# Sincronismo.net
KiCad netlist of a schematic drawn in Altium Designer
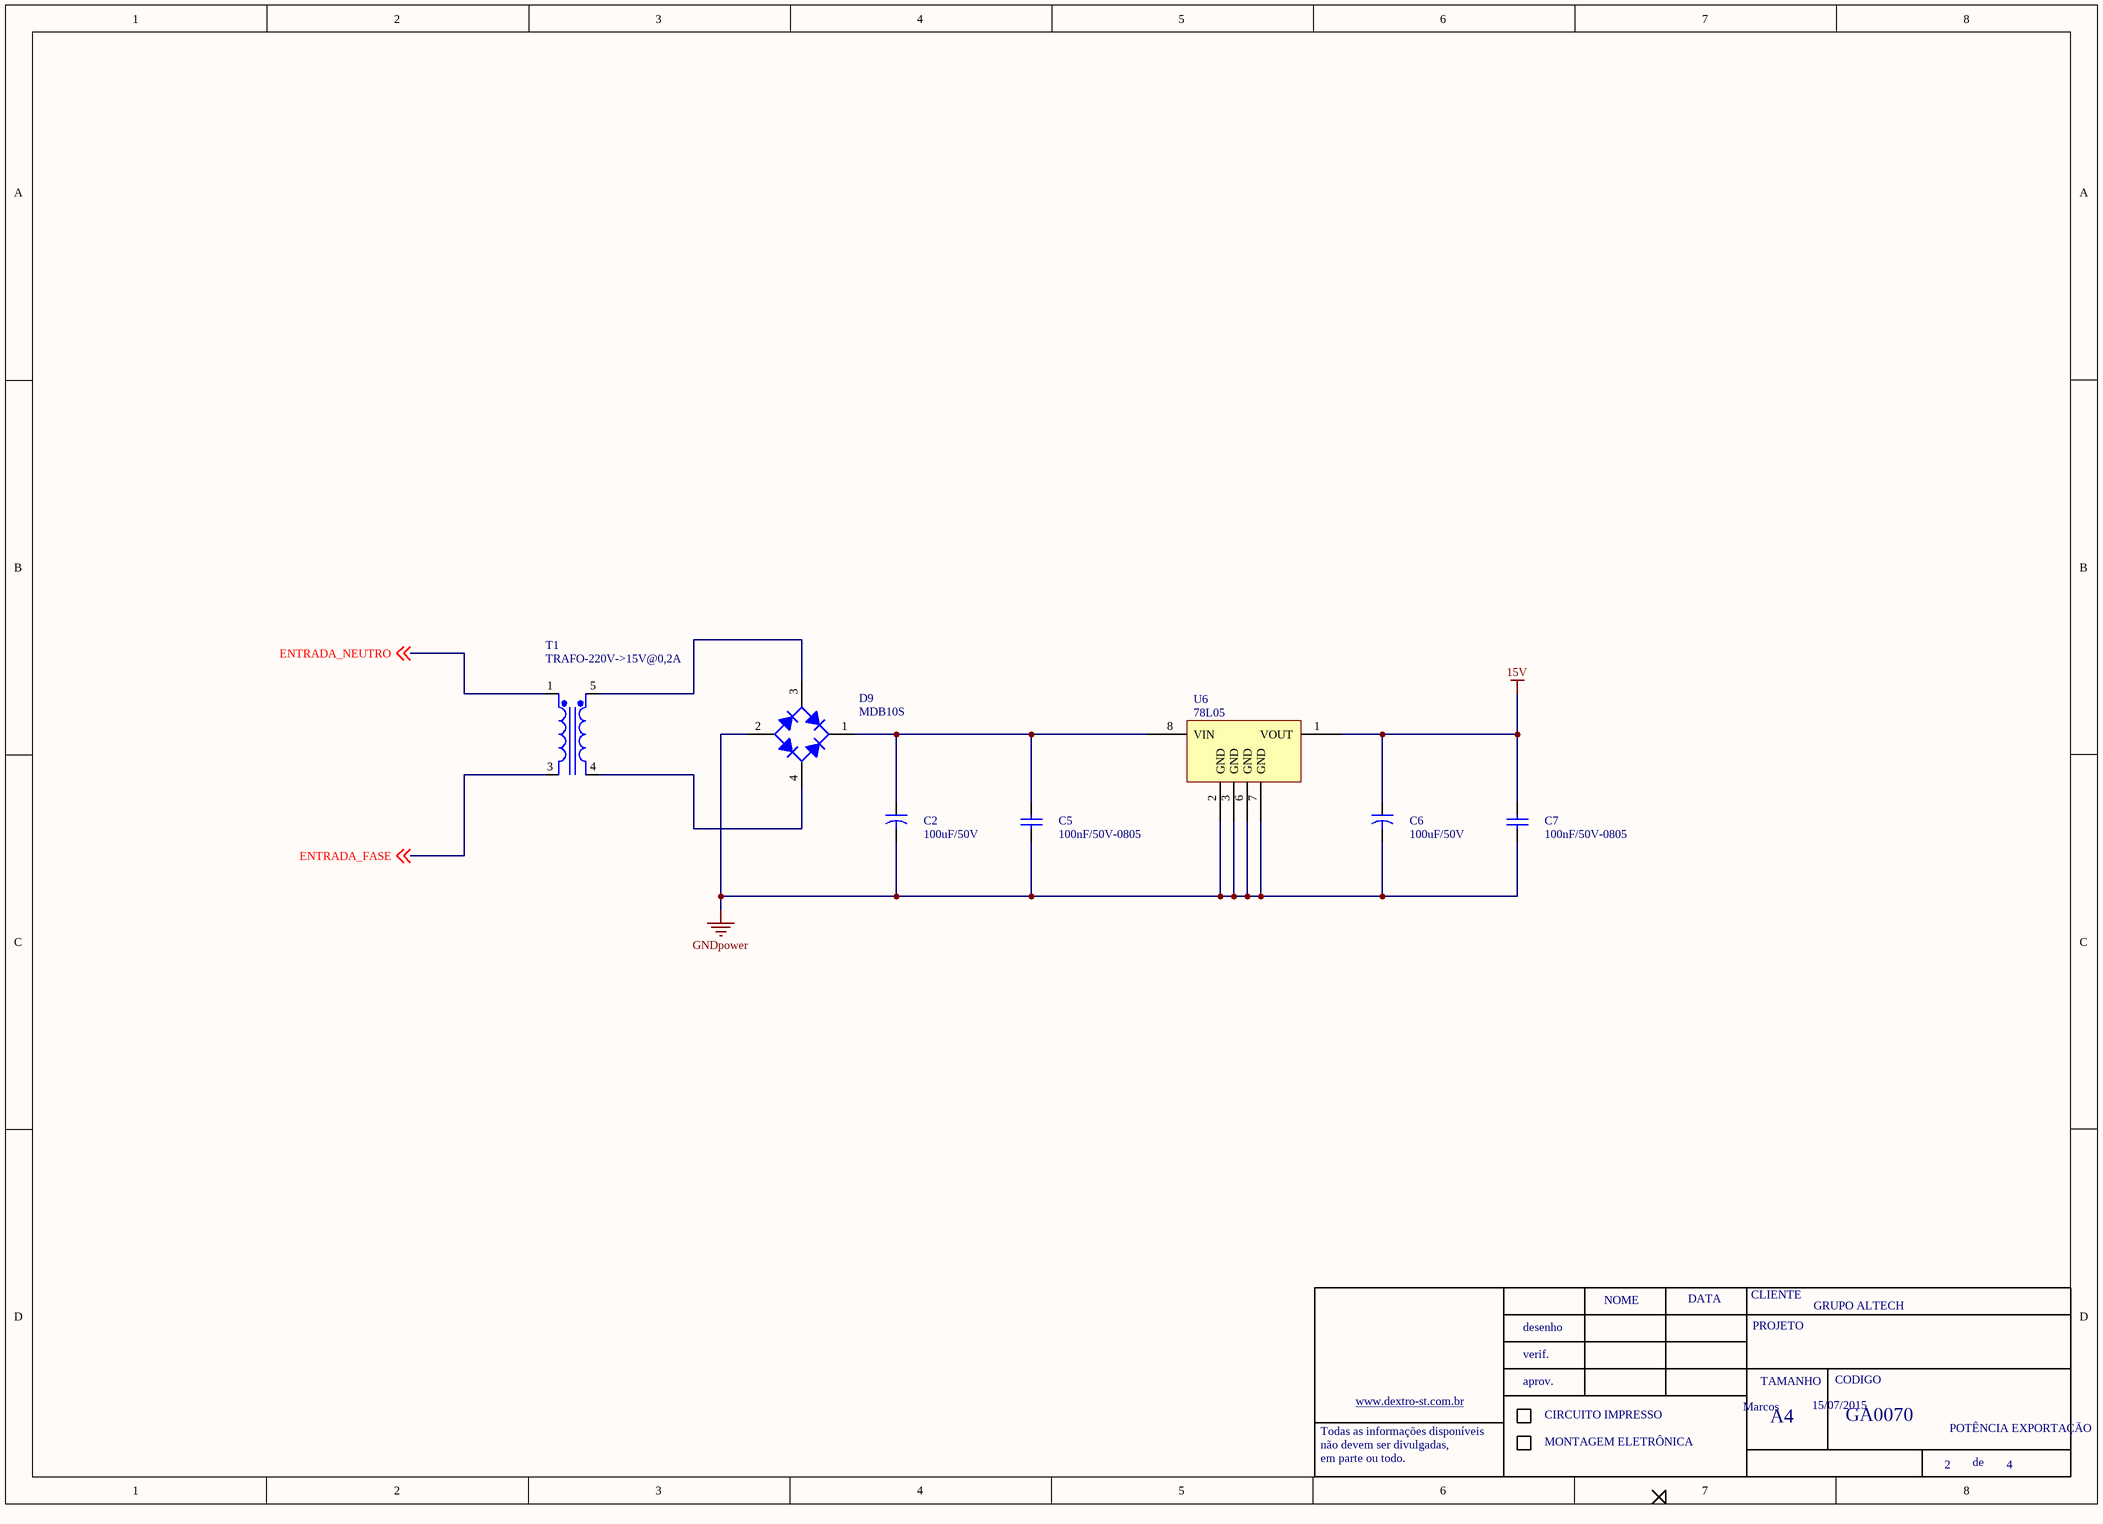
[diagram p0: Sincronismo.SchDoc]

(export (version "E")
  (design (tool "Eeschema 10.0.6"))
  (components
    (comp (ref "C2")
      (value "100uF/50V")
      (footprint "CAP POL 8x12mm")
      (libsource (lib "AquinoLib") (part "100uF/50V"))
    )
    (comp (ref "C5")
      (value "100nF/50V-0805")
      (footprint "0805-REVISADO ONDA")
      (libsource (lib "AquinoLib") (part "100nF/50-0805-NPO"))
    )
    (comp (ref "C6")
      (value "100uF/50V")
      (footprint "CAP POL 8x12mm")
      (libsource (lib "AquinoLib") (part "100uF/50V"))
    )
    (comp (ref "C7")
      (value "100nF/50V-0805")
      (footprint "0805-REVISADO ONDA")
      (libsource (lib "AquinoLib") (part "100nF/50-0805-NPO"))
    )
    (comp (ref "D9")
      (value "MDB10S")
      (footprint "MICRO DIP MDB10S")
      (libsource (lib "AquinoLib") (part "MDB10S"))
    )
    (comp (ref "T1")
      (value "TRAFO-220V->15V@0,2A")
      (description "TRAFO CORRENTE 1A-5V")
      (libsource (lib "ChaveDigital3") (part "TRAFO CORRENTE"))
    )
    (comp (ref "U6")
      (value "78L05")
      (footprint "SOIC-08")
      (libsource (lib "ChaveDigital3") (part "78L05-SOIC"))
    )
  )
  (nets
    (net (code "1") (name "15V") (class "Default")
      (node (ref "C6") (pin "1") (pinfunction "1_1") (pintype "passive"))
      (node (ref "C7") (pin "2") (pinfunction "2_2") (pintype "passive"))
      (node (ref "U6") (pin "1") (pinfunction "VOUT_1") (pintype "passive"))
    )
    (net (code "2") (name "ENTRADA_FASE") (class "Default")
      (node (ref "T1") (pin "3") (pinfunction "3_3") (pintype "passive"))
    )
    (net (code "3") (name "ENTRADA_NEUTRO") (class "Default")
      (node (ref "T1") (pin "1") (pinfunction "1_1") (pintype "passive"))
    )
    (net (code "4") (name "GNDpower") (class "Default")
      (node (ref "C2") (pin "2") (pinfunction "2_2") (pintype "passive"))
      (node (ref "C5") (pin "1") (pinfunction "1_1") (pintype "passive"))
      (node (ref "C6") (pin "2") (pinfunction "2_2") (pintype "passive"))
      (node (ref "C7") (pin "1") (pinfunction "1_1") (pintype "passive"))
      (node (ref "D9") (pin "2") (pinfunction "A_2") (pintype "passive"))
      (node (ref "U6") (pin "2") (pinfunction "GND_2") (pintype "passive"))
      (node (ref "U6") (pin "3") (pinfunction "GND_3") (pintype "passive"))
      (node (ref "U6") (pin "6") (pinfunction "GND_6") (pintype "passive"))
      (node (ref "U6") (pin "7") (pinfunction "GND_7") (pintype "passive"))
    )
    (net (code "5") (name "Net-(D9-C-Pad3)") (class "Default")
      (node (ref "D9") (pin "3") (pinfunction "C_3") (pintype "passive"))
      (node (ref "T1") (pin "5") (pinfunction "5_5") (pintype "passive"))
    )
    (net (code "6") (name "Net-(D9-C-Pad4)") (class "Default")
      (node (ref "D9") (pin "4") (pinfunction "C_4") (pintype "passive"))
      (node (ref "T1") (pin "4") (pinfunction "4_4") (pintype "passive"))
    )
    (net (code "7") (name "Net-(D9-K)") (class "Default")
      (node (ref "C2") (pin "1") (pinfunction "1_1") (pintype "passive"))
      (node (ref "C5") (pin "2") (pinfunction "2_2") (pintype "passive"))
      (node (ref "D9") (pin "1") (pinfunction "K_1") (pintype "passive"))
      (node (ref "U6") (pin "8") (pinfunction "VIN_8") (pintype "passive"))
    )
  )
)
